# IMU.net
KiCad netlist of a schematic drawn in Altium Designer
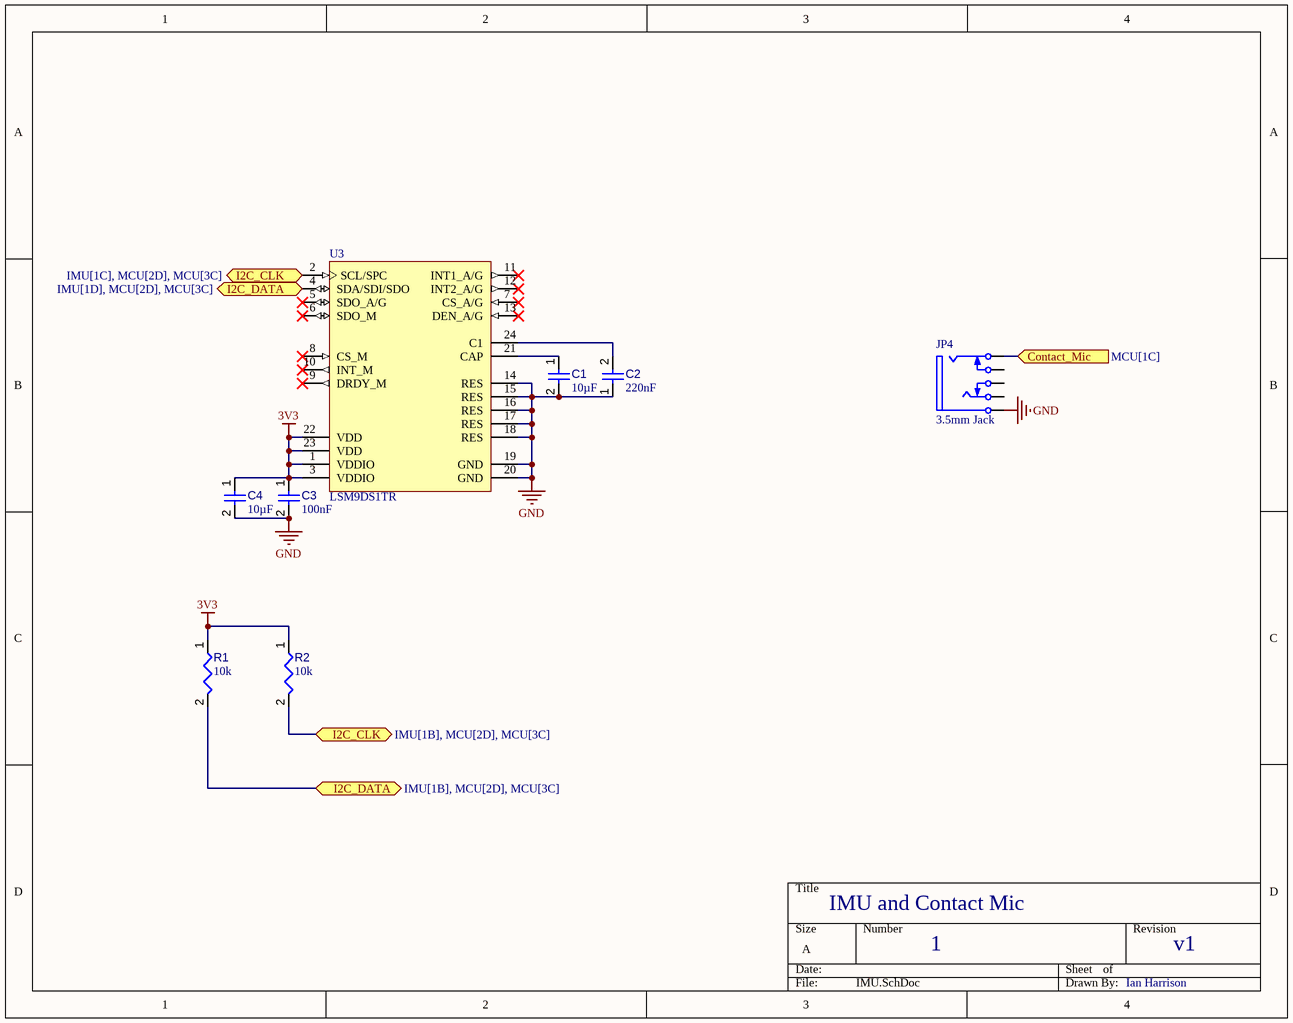
[diagram p0: IMU.SchDoc]

(export (version "E")
  (design (tool "Eeschema 10.0.6"))
  (components
    (comp (ref "C1")
      (value "10µF")
      (footprint "CAPC0603(1608)100_L")
      (description "Chip Capacitor, 10µF +/-20%, 10V, 0603, Thickness 1 mm")
      (fields (field (name "TOLERANCE") "10%") (field (name "Comment") "Capacitor 10µF +/-20% 10V 0603"))
      (libsource (lib "Ian Harrison") (part "CAP-NP-2"))
    )
    (comp (ref "C2")
      (value "220nF")
      (footprint "FP-C0603C-CF-IPC_B")
      (fields (field (name "Comment") "Capacitor 220 nF"))
      (libsource (lib "Ian Harrison") (part "CAP-NP-2"))
    )
    (comp (ref "C3")
      (value "100nF")
      (footprint "CAPC1608X90X40NL10T20")
      (description "Chip Capacitor, 100 nF, +/- 10%, 50 V, 0603 (1608 Metric)")
      (fields (field (name "TOLERANCE") "10%") (field (name "Comment") "Capacitor 100 nF +/-10% 50 V 0603"))
      (libsource (lib "Ian Harrison") (part "CAP-NP-2"))
    )
    (comp (ref "C4")
      (value "10µF")
      (footprint "CAPC0603(1608)100_L")
      (description "Chip Capacitor, 10µF +/-20%, 10V, 0603, Thickness 1 mm")
      (fields (field (name "TOLERANCE") "10%") (field (name "Comment") "Capacitor 10µF +/-20% 10V 0603"))
      (libsource (lib "Ian Harrison") (part "CAP-NP-2"))
    )
    (comp (ref "JP4")
      (value "3.5mm Jack")
      (footprint "SWIT-35RASMT4BHNTRX_V")
      (description "3 Pole(s), Surface Mount Terminal, Jack")
      (libsource (lib "Ian Harrison") (part "JACK-3CD5-RN"))
    )
    (comp (ref "R1")
      (value "10k")
      (footprint "RESC1608X55X25ML10T15")
      (description "Chip Resistor, 10 KOhm, +/- 1%, 01 W, -55 to 155 degC, 0603 (1608 Metric)")
      (fields (field (name "POWER") "100mW") (field (name "TOLERANCE") "1%"))
      (libsource (lib "Ian Harrison") (part "RES-2"))
    )
    (comp (ref "R2")
      (value "10k")
      (footprint "RESC1608X55X25ML10T15")
      (description "Chip Resistor, 10 KOhm, +/- 1%, 01 W, -55 to 155 degC, 0603 (1608 Metric)")
      (fields (field (name "POWER") "100mW") (field (name "TOLERANCE") "1%"))
      (libsource (lib "Ian Harrison") (part "RES-2"))
    )
    (comp (ref "U3")
      (value "LSM9DS1TR")
      (footprint "STM-LGA-24_3500X3000X1000")
      (fields (field (name "PARTNUMBER") "LSM9DS1") (field (name "MANUFACTURER") "STMicroelectronics"))
      (libsource (lib "Altium Content Vault") (part "STM-LSM9DS1-24"))
    )
  )
  (nets
    (net (code "1") (name "/Contact_Mic") (class "Default")
      (node (ref "JP4") (pin "2") (pinfunction "2_2") (pintype "passive"))
    )
    (net (code "2") (name "/I2C_CLK") (class "Default")
      (node (ref "R2") (pin "2") (pinfunction "2_2") (pintype "passive"))
      (node (ref "U3") (pin "2") (pinfunction "SCL/SPC_2") (pintype "input"))
    )
    (net (code "3") (name "/I2C_DATA") (class "Default")
      (node (ref "R1") (pin "2") (pinfunction "2_2") (pintype "passive"))
      (node (ref "U3") (pin "4") (pinfunction "SDA/SDI/SDO_4") (pintype "bidirectional"))
    )
    (net (code "4") (name "3V3") (class "Default")
      (node (ref "C3") (pin "1") (pinfunction "1_1") (pintype "passive"))
      (node (ref "C4") (pin "1") (pinfunction "1_1") (pintype "passive"))
      (node (ref "R1") (pin "1") (pinfunction "1_1") (pintype "passive"))
      (node (ref "R2") (pin "1") (pinfunction "1_1") (pintype "passive"))
      (node (ref "U3") (pin "1") (pinfunction "VDDIO_1") (pintype "power_in"))
      (node (ref "U3") (pin "22") (pinfunction "VDD_22") (pintype "power_in"))
      (node (ref "U3") (pin "23") (pinfunction "VDD_23") (pintype "power_in"))
      (node (ref "U3") (pin "3") (pinfunction "VDDIO_3") (pintype "power_in"))
    )
    (net (code "5") (name "GND") (class "Default")
      (node (ref "C1") (pin "2") (pinfunction "2_2") (pintype "passive"))
      (node (ref "C2") (pin "1") (pinfunction "1_1") (pintype "passive"))
      (node (ref "C3") (pin "2") (pinfunction "2_2") (pintype "passive"))
      (node (ref "C4") (pin "2") (pinfunction "2_2") (pintype "passive"))
      (node (ref "JP4") (pin "1") (pinfunction "1_1") (pintype "passive"))
      (node (ref "U3") (pin "14") (pinfunction "RES_14") (pintype "passive"))
      (node (ref "U3") (pin "15") (pinfunction "RES_15") (pintype "passive"))
      (node (ref "U3") (pin "16") (pinfunction "RES_16") (pintype "passive"))
      (node (ref "U3") (pin "17") (pinfunction "RES_17") (pintype "passive"))
      (node (ref "U3") (pin "18") (pinfunction "RES_18") (pintype "passive"))
      (node (ref "U3") (pin "19") (pinfunction "GND_19") (pintype "power_in"))
      (node (ref "U3") (pin "20") (pinfunction "GND_20") (pintype "power_in"))
    )
    (net (code "6") (name "Net-(U3-C1)") (class "Default")
      (node (ref "C2") (pin "2") (pinfunction "2_2") (pintype "passive"))
      (node (ref "U3") (pin "24") (pinfunction "C1_24") (pintype "passive"))
    )
    (net (code "7") (name "Net-(U3-CAP)") (class "Default")
      (node (ref "C1") (pin "1") (pinfunction "1_1") (pintype "passive"))
      (node (ref "U3") (pin "21") (pinfunction "CAP_21") (pintype "passive"))
    )
    (net (code "8") (name "unconnected-(JP4-Pad3)") (class "Default")
      (node (ref "JP4") (pin "3") (pinfunction "3_3") (pintype "passive"))
    )
    (net (code "9") (name "unconnected-(JP4-Pad4)") (class "Default")
      (node (ref "JP4") (pin "4") (pinfunction "4_4") (pintype "passive"))
    )
    (net (code "10") (name "unconnected-(JP4-Pad5)") (class "Default")
      (node (ref "JP4") (pin "5") (pinfunction "5_5") (pintype "passive"))
    )
    (net (code "11") (name "unconnected-(U3-CS_A{slash}G-Pad7)") (class "Default")
      (node (ref "U3") (pin "7") (pinfunction "CS_A/G_7") (pintype "input+no_connect"))
    )
    (net (code "12") (name "unconnected-(U3-CS_M-Pad8)") (class "Default")
      (node (ref "U3") (pin "8") (pinfunction "CS_M_8") (pintype "input+no_connect"))
    )
    (net (code "13") (name "unconnected-(U3-DEN_A{slash}G-Pad13)") (class "Default")
      (node (ref "U3") (pin "13") (pinfunction "DEN_A/G_13") (pintype "input+no_connect"))
    )
    (net (code "14") (name "unconnected-(U3-DRDY_M-Pad9)") (class "Default")
      (node (ref "U3") (pin "9") (pinfunction "DRDY_M_9") (pintype "output+no_connect"))
    )
    (net (code "15") (name "unconnected-(U3-INT1_A{slash}G-Pad11)") (class "Default")
      (node (ref "U3") (pin "11") (pinfunction "INT1_A/G_11") (pintype "output+no_connect"))
    )
    (net (code "16") (name "unconnected-(U3-INT2_A{slash}G-Pad12)") (class "Default")
      (node (ref "U3") (pin "12") (pinfunction "INT2_A/G_12") (pintype "output+no_connect"))
    )
    (net (code "17") (name "unconnected-(U3-INT_M-Pad10)") (class "Default")
      (node (ref "U3") (pin "10") (pinfunction "INT_M_10") (pintype "output+no_connect"))
    )
    (net (code "18") (name "unconnected-(U3-SDO_A{slash}G-Pad5)") (class "Default")
      (node (ref "U3") (pin "5") (pinfunction "SDO_A/G_5") (pintype "bidirectional+no_connect"))
    )
    (net (code "19") (name "unconnected-(U3-SDO_M-Pad6)") (class "Default")
      (node (ref "U3") (pin "6") (pinfunction "SDO_M_6") (pintype "bidirectional+no_connect"))
    )
  )
)
